# ControlePotencia.net
KiCad netlist of a schematic drawn in Altium Designer
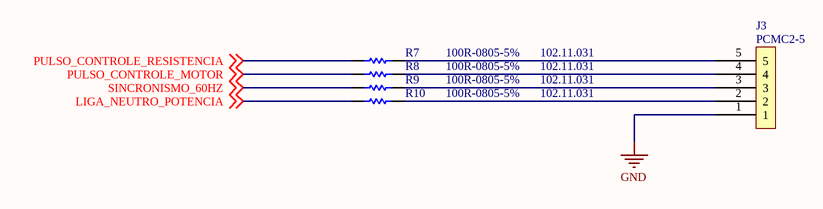
[diagram p0: ControlePotencia.SchDoc]

(export (version "E")
  (design (tool "Eeschema 10.0.6"))
  (components
    (comp (ref "J3") (value "PCMC2-5") (footprint "PCMC2-5") (libsource (lib "AquinoLib") (part "PCMC2-5")))
    (comp (ref "R7")
      (value "100R-0805-5%")
      (footprint "0805-REVISADO ONDA")
      (fields (field (name "ERP") "102.11.031"))
      (libsource (lib "AquinoLib") (part "100R-0805-5%"))
    )
    (comp (ref "R8")
      (value "100R-0805-5%")
      (footprint "0805-REVISADO ONDA")
      (fields (field (name "ERP") "102.11.031"))
      (libsource (lib "AquinoLib") (part "100R-0805-5%"))
    )
    (comp (ref "R9")
      (value "100R-0805-5%")
      (footprint "0805-REVISADO ONDA")
      (fields (field (name "ERP") "102.11.031"))
      (libsource (lib "AquinoLib") (part "100R-0805-5%"))
    )
    (comp (ref "R10")
      (value "100R-0805-5%")
      (footprint "0805-REVISADO ONDA")
      (fields (field (name "ERP") "102.11.031"))
      (libsource (lib "AquinoLib") (part "100R-0805-5%"))
    )
  )
  (nets
    (net (code "1") (name "GND") (class "Default")
      (node (ref "J3") (pin "1") (pinfunction "1_1") (pintype "passive"))
    )
    (net (code "2") (name "LIGA_NEUTRO_POTENCIA") (class "Default")
      (node (ref "R10") (pin "1") (pinfunction "1_1") (pintype "passive"))
    )
    (net (code "3") (name "Net-(J3-Pad2)") (class "Default")
      (node (ref "J3") (pin "2") (pinfunction "2_2") (pintype "passive"))
      (node (ref "R10") (pin "2") (pinfunction "2_2") (pintype "passive"))
    )
    (net (code "4") (name "Net-(J3-Pad3)") (class "Default")
      (node (ref "J3") (pin "3") (pinfunction "3_3") (pintype "passive"))
      (node (ref "R9") (pin "2") (pinfunction "2_2") (pintype "passive"))
    )
    (net (code "5") (name "Net-(J3-Pad4)") (class "Default")
      (node (ref "J3") (pin "4") (pinfunction "4_4") (pintype "passive"))
      (node (ref "R8") (pin "2") (pinfunction "2_2") (pintype "passive"))
    )
    (net (code "6") (name "Net-(J3-Pad5)") (class "Default")
      (node (ref "J3") (pin "5") (pinfunction "5_5") (pintype "passive"))
      (node (ref "R7") (pin "2") (pinfunction "2_2") (pintype "passive"))
    )
    (net (code "7") (name "PULSO_CONTROLE_MOTOR") (class "Default")
      (node (ref "R8") (pin "1") (pinfunction "1_1") (pintype "passive"))
    )
    (net (code "8") (name "PULSO_CONTROLE_RESISTENCIA") (class "Default")
      (node (ref "R7") (pin "1") (pinfunction "1_1") (pintype "passive"))
    )
    (net (code "9") (name "SINCRONISMO_60HZ") (class "Default")
      (node (ref "R9") (pin "1") (pinfunction "1_1") (pintype "passive"))
    )
  )
)
